# Switches.net
KiCad netlist of a schematic drawn in Altium Designer
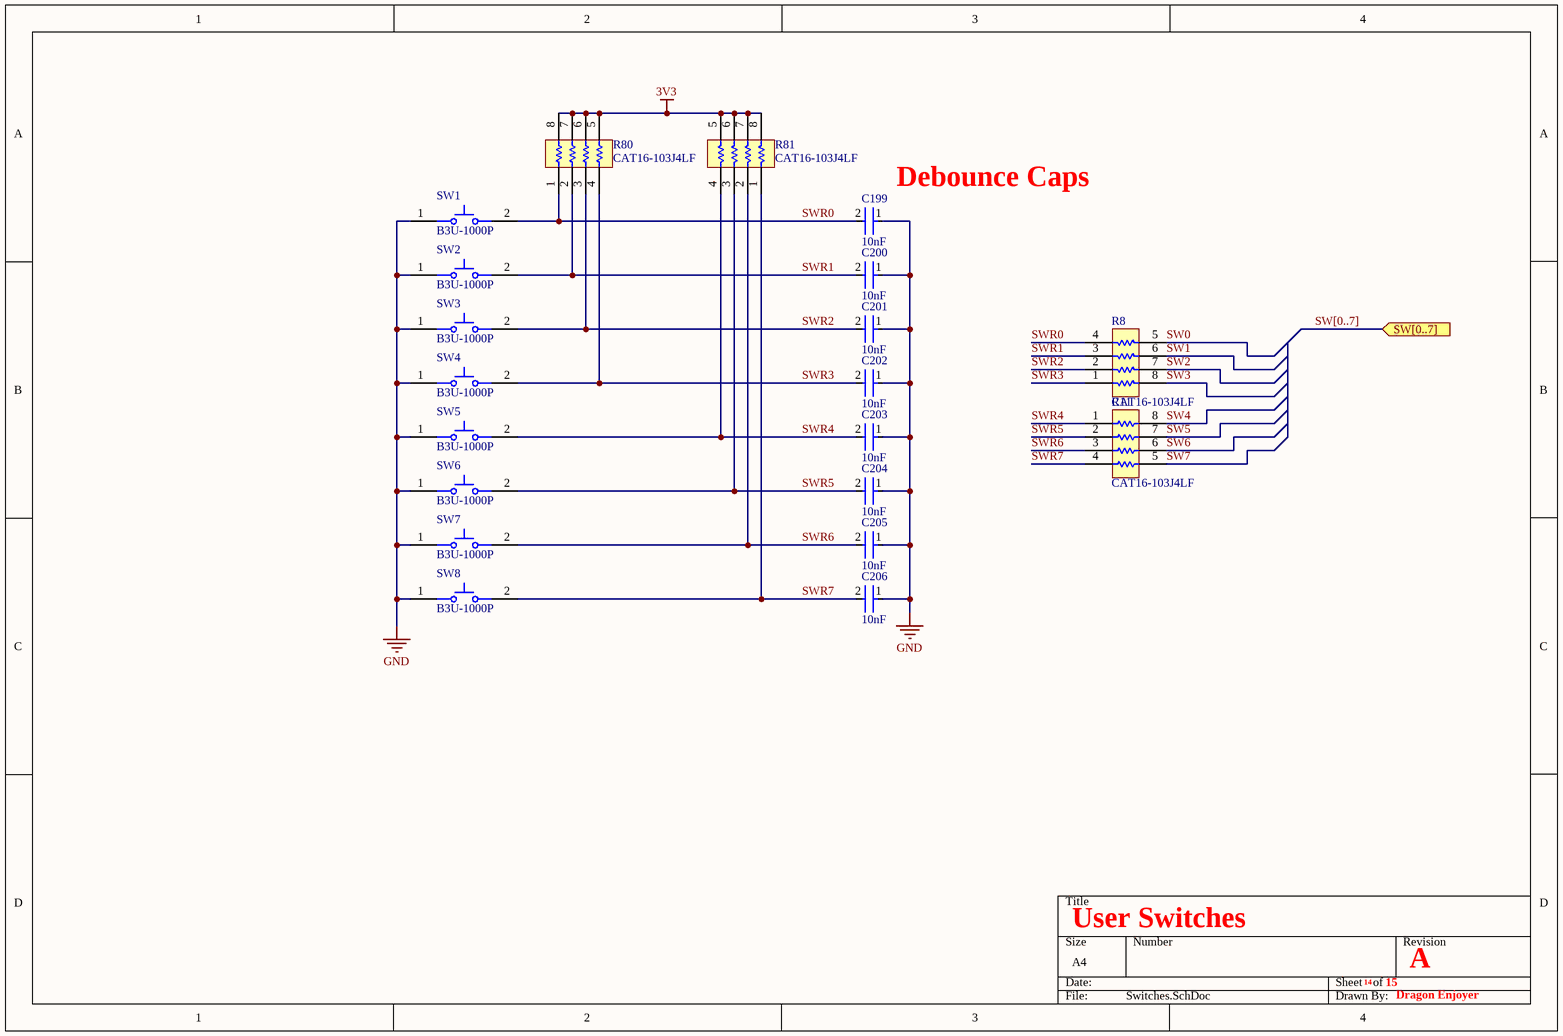
[diagram p0: Switches.SchDoc]

(export (version "E")
  (design (tool "Eeschema 10.0.6"))
  (components
    (comp (ref "C199")
      (value "GRM155R71H103KA88D")
      (footprint "FP-GRM155-0_05-IPC_C")
      (description "Chip Multilayer Ceramic Capacitors for General Purpose, 0402, 10000pF, X7R, 15%, 10%, 50V")
      (fields
        (field (name "TOLERANCE") "10%")
        (field (name "VOLTAGE") "25V")
        (field (name "CAPACITANCE") "10nF")
      )
      (libsource (lib "Altium Content Vault") (part "02cd4be3c70576c341d710602a673aa"))
    )
    (comp (ref "C200")
      (value "GRM155R71H103KA88D")
      (footprint "FP-GRM155-0_05-IPC_C")
      (description "Chip Multilayer Ceramic Capacitors for General Purpose, 0402, 10000pF, X7R, 15%, 10%, 50V")
      (fields
        (field (name "TOLERANCE") "10%")
        (field (name "VOLTAGE") "25V")
        (field (name "CAPACITANCE") "10nF")
      )
      (libsource (lib "Altium Content Vault") (part "02cd4be3c70576c341d710602a673aa"))
    )
    (comp (ref "C201")
      (value "GRM155R71H103KA88D")
      (footprint "FP-GRM155-0_05-IPC_C")
      (description "Chip Multilayer Ceramic Capacitors for General Purpose, 0402, 10000pF, X7R, 15%, 10%, 50V")
      (fields
        (field (name "TOLERANCE") "10%")
        (field (name "VOLTAGE") "25V")
        (field (name "CAPACITANCE") "10nF")
      )
      (libsource (lib "Altium Content Vault") (part "02cd4be3c70576c341d710602a673aa"))
    )
    (comp (ref "C202")
      (value "GRM155R71H103KA88D")
      (footprint "FP-GRM155-0_05-IPC_C")
      (description "Chip Multilayer Ceramic Capacitors for General Purpose, 0402, 10000pF, X7R, 15%, 10%, 50V")
      (fields
        (field (name "TOLERANCE") "10%")
        (field (name "VOLTAGE") "25V")
        (field (name "CAPACITANCE") "10nF")
      )
      (libsource (lib "Altium Content Vault") (part "02cd4be3c70576c341d710602a673aa"))
    )
    (comp (ref "C203")
      (value "GRM155R71H103KA88D")
      (footprint "FP-GRM155-0_05-IPC_C")
      (description "Chip Multilayer Ceramic Capacitors for General Purpose, 0402, 10000pF, X7R, 15%, 10%, 50V")
      (fields
        (field (name "TOLERANCE") "10%")
        (field (name "VOLTAGE") "25V")
        (field (name "CAPACITANCE") "10nF")
      )
      (libsource (lib "Altium Content Vault") (part "02cd4be3c70576c341d710602a673aa"))
    )
    (comp (ref "C204")
      (value "GRM155R71H103KA88D")
      (footprint "FP-GRM155-0_05-IPC_C")
      (description "Chip Multilayer Ceramic Capacitors for General Purpose, 0402, 10000pF, X7R, 15%, 10%, 50V")
      (fields
        (field (name "TOLERANCE") "10%")
        (field (name "VOLTAGE") "25V")
        (field (name "CAPACITANCE") "10nF")
      )
      (libsource (lib "Altium Content Vault") (part "02cd4be3c70576c341d710602a673aa"))
    )
    (comp (ref "C205")
      (value "GRM155R71H103KA88D")
      (footprint "FP-GRM155-0_05-IPC_C")
      (description "Chip Multilayer Ceramic Capacitors for General Purpose, 0402, 10000pF, X7R, 15%, 10%, 50V")
      (fields
        (field (name "TOLERANCE") "10%")
        (field (name "VOLTAGE") "25V")
        (field (name "CAPACITANCE") "10nF")
      )
      (libsource (lib "Altium Content Vault") (part "02cd4be3c70576c341d710602a673aa"))
    )
    (comp (ref "C206")
      (value "GRM155R71H103KA88D")
      (footprint "FP-GRM155-0_05-IPC_C")
      (description "Chip Multilayer Ceramic Capacitors for General Purpose, 0402, 10000pF, X7R, 15%, 10%, 50V")
      (fields
        (field (name "TOLERANCE") "10%")
        (field (name "VOLTAGE") "25V")
        (field (name "CAPACITANCE") "10nF")
      )
      (libsource (lib "Altium Content Vault") (part "02cd4be3c70576c341d710602a673aa"))
    )
    (comp (ref "R8")
      (value "CAT16-103J4LF")
      (footprint "BOUR-CAT16-103J4LF_L")
      (fields (field (name "MANUFACTURER") "Bourns") (field (name "TOLERANCE") "±5%"))
      (libsource (lib "") (part "RES-P-8_1"))
    )
    (comp (ref "R11")
      (value "CAT16-103J4LF")
      (footprint "BOUR-CAT16-103J4LF_L")
      (fields (field (name "MANUFACTURER") "Bourns") (field (name "TOLERANCE") "±5%"))
      (libsource (lib "Altium Content Vault") (part "RES-P-8"))
    )
    (comp (ref "R80")
      (value "CAT16-103J4LF")
      (footprint "BOUR-CAT16-103J4LF_L")
      (fields (field (name "MANUFACTURER") "Bourns") (field (name "TOLERANCE") "±5%"))
      (libsource (lib "") (part "RES-P-8_1"))
    )
    (comp (ref "R81")
      (value "CAT16-103J4LF")
      (footprint "BOUR-CAT16-103J4LF_L")
      (fields (field (name "MANUFACTURER") "Bourns") (field (name "TOLERANCE") "±5%"))
      (libsource (lib "Altium Content Vault") (part "RES-P-8"))
    )
    (comp (ref "SW1")
      (value "B3U-1000P")
      (footprint "OMRON-B3U-1000_V")
      (description "Tactile Switch, SPST-NO, 0.05 A, 12 V, -25 to 70 degC, 2-Pin SMD, RoHS, Tape and Reel")
      (fields (field (name "MANUFACTURER") "Omron Electronic Components"))
      (libsource (lib "Main Workspace") (part "SW-SPST-NO-2"))
    )
    (comp (ref "SW2")
      (value "B3U-1000P")
      (footprint "OMRON-B3U-1000_V")
      (description "Tactile Switch, SPST-NO, 0.05 A, 12 V, -25 to 70 degC, 2-Pin SMD, RoHS, Tape and Reel")
      (fields (field (name "MANUFACTURER") "Omron Electronic Components"))
      (libsource (lib "Main Workspace") (part "SW-SPST-NO-2"))
    )
    (comp (ref "SW3")
      (value "B3U-1000P")
      (footprint "OMRON-B3U-1000_V")
      (description "Tactile Switch, SPST-NO, 0.05 A, 12 V, -25 to 70 degC, 2-Pin SMD, RoHS, Tape and Reel")
      (fields (field (name "MANUFACTURER") "Omron Electronic Components"))
      (libsource (lib "Main Workspace") (part "SW-SPST-NO-2"))
    )
    (comp (ref "SW4")
      (value "B3U-1000P")
      (footprint "OMRON-B3U-1000_V")
      (description "Tactile Switch, SPST-NO, 0.05 A, 12 V, -25 to 70 degC, 2-Pin SMD, RoHS, Tape and Reel")
      (fields (field (name "MANUFACTURER") "Omron Electronic Components"))
      (libsource (lib "Main Workspace") (part "SW-SPST-NO-2"))
    )
    (comp (ref "SW5")
      (value "B3U-1000P")
      (footprint "OMRON-B3U-1000_V")
      (description "Tactile Switch, SPST-NO, 0.05 A, 12 V, -25 to 70 degC, 2-Pin SMD, RoHS, Tape and Reel")
      (fields (field (name "MANUFACTURER") "Omron Electronic Components"))
      (libsource (lib "Main Workspace") (part "SW-SPST-NO-2"))
    )
    (comp (ref "SW6")
      (value "B3U-1000P")
      (footprint "OMRON-B3U-1000_V")
      (description "Tactile Switch, SPST-NO, 0.05 A, 12 V, -25 to 70 degC, 2-Pin SMD, RoHS, Tape and Reel")
      (fields (field (name "MANUFACTURER") "Omron Electronic Components"))
      (libsource (lib "Main Workspace") (part "SW-SPST-NO-2"))
    )
    (comp (ref "SW7")
      (value "B3U-1000P")
      (footprint "OMRON-B3U-1000_V")
      (description "Tactile Switch, SPST-NO, 0.05 A, 12 V, -25 to 70 degC, 2-Pin SMD, RoHS, Tape and Reel")
      (fields (field (name "MANUFACTURER") "Omron Electronic Components"))
      (libsource (lib "Main Workspace") (part "SW-SPST-NO-2"))
    )
    (comp (ref "SW8")
      (value "B3U-1000P")
      (footprint "OMRON-B3U-1000_V")
      (description "Tactile Switch, SPST-NO, 0.05 A, 12 V, -25 to 70 degC, 2-Pin SMD, RoHS, Tape and Reel")
      (fields (field (name "MANUFACTURER") "Omron Electronic Components"))
      (libsource (lib "Main Workspace") (part "SW-SPST-NO-2"))
    )
  )
  (nets
    (net (code "1") (name "/SW0") (class "Default")
      (node (ref "R8") (pin "5") (pinfunction "5_5") (pintype "passive"))
    )
    (net (code "2") (name "/SW1") (class "Default")
      (node (ref "R8") (pin "6") (pinfunction "6_6") (pintype "passive"))
    )
    (net (code "3") (name "/SW2") (class "Default")
      (node (ref "R8") (pin "7") (pinfunction "7_7") (pintype "passive"))
    )
    (net (code "4") (name "/SW3") (class "Default")
      (node (ref "R8") (pin "8") (pinfunction "8_8") (pintype "passive"))
    )
    (net (code "5") (name "/SW4") (class "Default")
      (node (ref "R11") (pin "8") (pinfunction "8_8") (pintype "passive"))
    )
    (net (code "6") (name "/SW5") (class "Default")
      (node (ref "R11") (pin "7") (pinfunction "7_7") (pintype "passive"))
    )
    (net (code "7") (name "/SW6") (class "Default")
      (node (ref "R11") (pin "6") (pinfunction "6_6") (pintype "passive"))
    )
    (net (code "8") (name "/SW7") (class "Default")
      (node (ref "R11") (pin "5") (pinfunction "5_5") (pintype "passive"))
    )
    (net (code "9") (name "/SWR0") (class "Default")
      (node (ref "C199") (pin "2") (pinfunction "2_2") (pintype "passive"))
      (node (ref "R8") (pin "4") (pinfunction "4_4") (pintype "passive"))
      (node (ref "R80") (pin "1") (pinfunction "1_1") (pintype "passive"))
      (node (ref "SW1") (pin "2") (pinfunction "2_2") (pintype "passive"))
    )
    (net (code "10") (name "/SWR1") (class "Default")
      (node (ref "C200") (pin "2") (pinfunction "2_2") (pintype "passive"))
      (node (ref "R8") (pin "3") (pinfunction "3_3") (pintype "passive"))
      (node (ref "R80") (pin "2") (pinfunction "2_2") (pintype "passive"))
      (node (ref "SW2") (pin "2") (pinfunction "2_2") (pintype "passive"))
    )
    (net (code "11") (name "/SWR2") (class "Default")
      (node (ref "C201") (pin "2") (pinfunction "2_2") (pintype "passive"))
      (node (ref "R8") (pin "2") (pinfunction "2_2") (pintype "passive"))
      (node (ref "R80") (pin "3") (pinfunction "3_3") (pintype "passive"))
      (node (ref "SW3") (pin "2") (pinfunction "2_2") (pintype "passive"))
    )
    (net (code "12") (name "/SWR3") (class "Default")
      (node (ref "C202") (pin "2") (pinfunction "2_2") (pintype "passive"))
      (node (ref "R8") (pin "1") (pinfunction "1_1") (pintype "passive"))
      (node (ref "R80") (pin "4") (pinfunction "4_4") (pintype "passive"))
      (node (ref "SW4") (pin "2") (pinfunction "2_2") (pintype "passive"))
    )
    (net (code "13") (name "/SWR4") (class "Default")
      (node (ref "C203") (pin "2") (pinfunction "2_2") (pintype "passive"))
      (node (ref "R11") (pin "1") (pinfunction "1_1") (pintype "passive"))
      (node (ref "R81") (pin "4") (pinfunction "4_4") (pintype "passive"))
      (node (ref "SW5") (pin "2") (pinfunction "2_2") (pintype "passive"))
    )
    (net (code "14") (name "/SWR5") (class "Default")
      (node (ref "C204") (pin "2") (pinfunction "2_2") (pintype "passive"))
      (node (ref "R11") (pin "2") (pinfunction "2_2") (pintype "passive"))
      (node (ref "R81") (pin "3") (pinfunction "3_3") (pintype "passive"))
      (node (ref "SW6") (pin "2") (pinfunction "2_2") (pintype "passive"))
    )
    (net (code "15") (name "/SWR6") (class "Default")
      (node (ref "C205") (pin "2") (pinfunction "2_2") (pintype "passive"))
      (node (ref "R11") (pin "3") (pinfunction "3_3") (pintype "passive"))
      (node (ref "R81") (pin "2") (pinfunction "2_2") (pintype "passive"))
      (node (ref "SW7") (pin "2") (pinfunction "2_2") (pintype "passive"))
    )
    (net (code "16") (name "/SWR7") (class "Default")
      (node (ref "C206") (pin "2") (pinfunction "2_2") (pintype "passive"))
      (node (ref "R11") (pin "4") (pinfunction "4_4") (pintype "passive"))
      (node (ref "R81") (pin "1") (pinfunction "1_1") (pintype "passive"))
      (node (ref "SW8") (pin "2") (pinfunction "2_2") (pintype "passive"))
    )
    (net (code "18") (name "3V3") (class "Default")
      (node (ref "R80") (pin "5") (pinfunction "5_5") (pintype "passive"))
      (node (ref "R80") (pin "6") (pinfunction "6_6") (pintype "passive"))
      (node (ref "R80") (pin "7") (pinfunction "7_7") (pintype "passive"))
      (node (ref "R80") (pin "8") (pinfunction "8_8") (pintype "passive"))
      (node (ref "R81") (pin "5") (pinfunction "5_5") (pintype "passive"))
      (node (ref "R81") (pin "6") (pinfunction "6_6") (pintype "passive"))
      (node (ref "R81") (pin "7") (pinfunction "7_7") (pintype "passive"))
      (node (ref "R81") (pin "8") (pinfunction "8_8") (pintype "passive"))
    )
    (net (code "19") (name "GND") (class "Default")
      (node (ref "C199") (pin "1") (pinfunction "1_1") (pintype "passive"))
      (node (ref "C200") (pin "1") (pinfunction "1_1") (pintype "passive"))
      (node (ref "C201") (pin "1") (pinfunction "1_1") (pintype "passive"))
      (node (ref "C202") (pin "1") (pinfunction "1_1") (pintype "passive"))
      (node (ref "C203") (pin "1") (pinfunction "1_1") (pintype "passive"))
      (node (ref "C204") (pin "1") (pinfunction "1_1") (pintype "passive"))
      (node (ref "C205") (pin "1") (pinfunction "1_1") (pintype "passive"))
      (node (ref "C206") (pin "1") (pinfunction "1_1") (pintype "passive"))
      (node (ref "SW1") (pin "1") (pinfunction "1_1") (pintype "passive"))
      (node (ref "SW2") (pin "1") (pinfunction "1_1") (pintype "passive"))
      (node (ref "SW3") (pin "1") (pinfunction "1_1") (pintype "passive"))
      (node (ref "SW4") (pin "1") (pinfunction "1_1") (pintype "passive"))
      (node (ref "SW5") (pin "1") (pinfunction "1_1") (pintype "passive"))
      (node (ref "SW6") (pin "1") (pinfunction "1_1") (pintype "passive"))
      (node (ref "SW7") (pin "1") (pinfunction "1_1") (pintype "passive"))
      (node (ref "SW8") (pin "1") (pinfunction "1_1") (pintype "passive"))
    )
  )
)
